# YNM-3000-1.net
KiCad netlist of a schematic drawn in Altium Designer
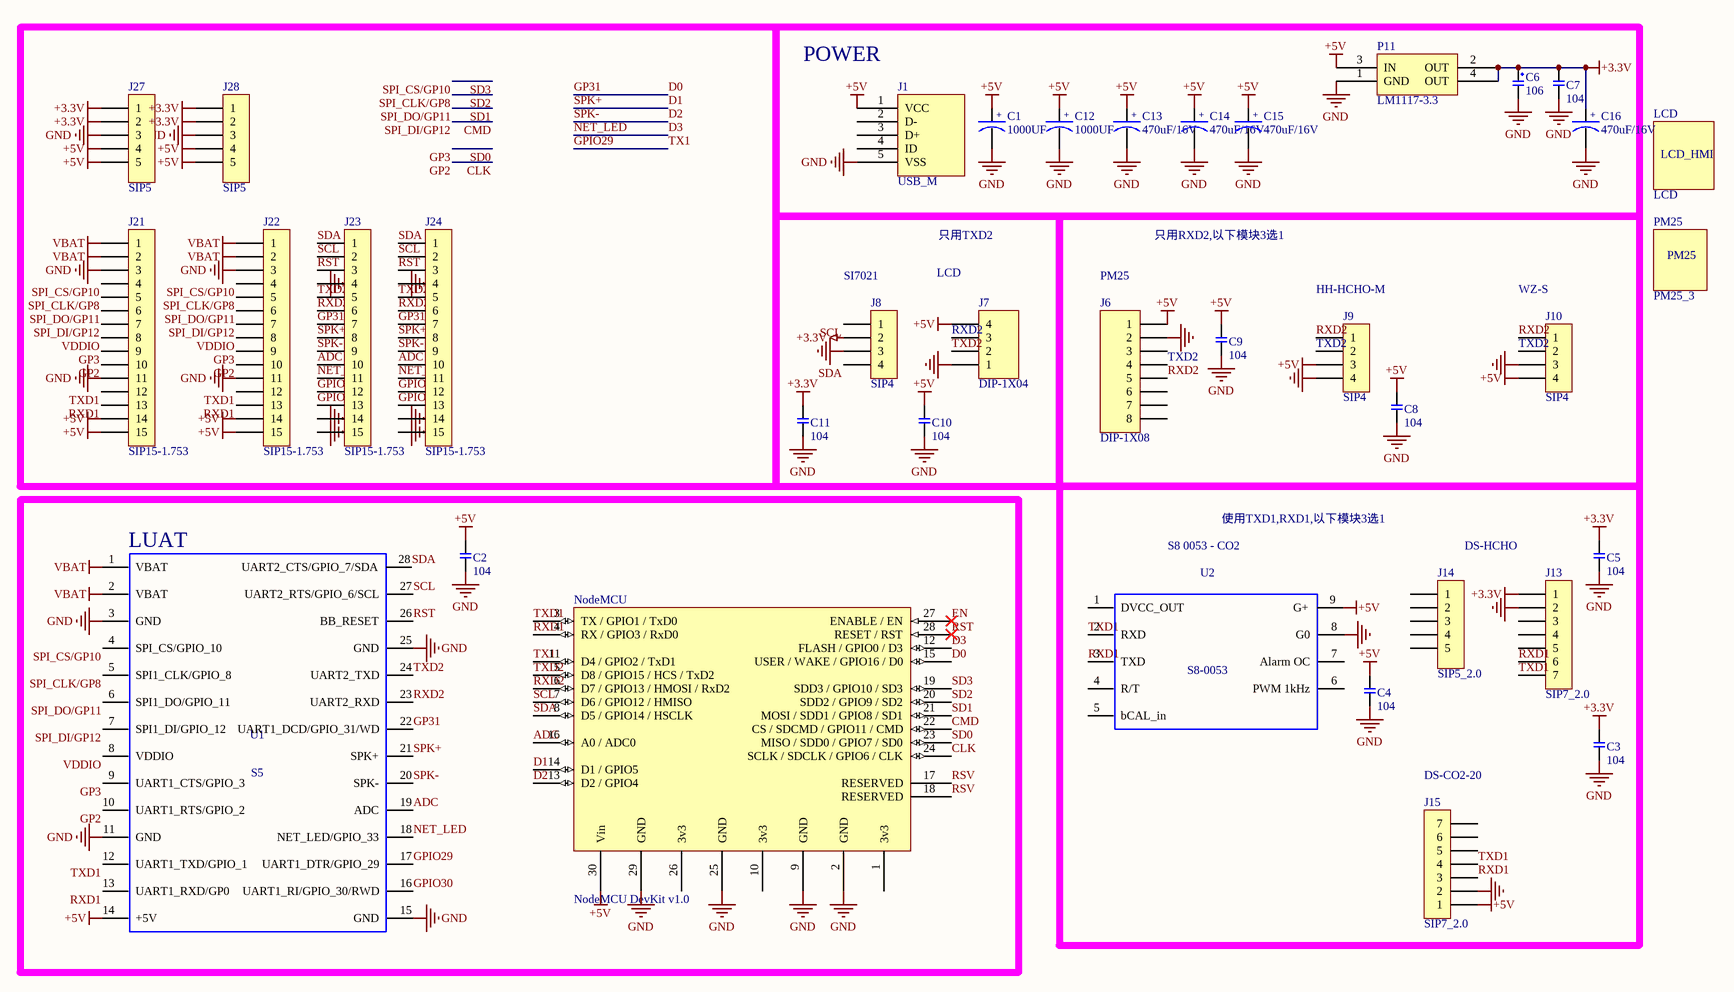
[diagram p0: YNM-3000-1.SchDoc]

(export (version "E")
  (design (tool "Eeschema 10.0.6"))
  (components
    (comp (ref "C1")
      (value "1000UF")
      (footprint "SMD-EC-F10")
      (description "体积（10*10.2MM）")
      (libsource (lib "wyf") (part "SMD-EC-F10"))
    )
    (comp (ref "C2")
      (value "104")
      (footprint "CAP-SMD-0603")
      (description "Cap0603")
      (libsource (lib "wyf") (part "Cap0603"))
    )
    (comp (ref "C3")
      (value "104")
      (footprint "CAP-SMD-0603")
      (description "Cap0603")
      (libsource (lib "wyf") (part "Cap0603"))
    )
    (comp (ref "C4")
      (value "104")
      (footprint "CAP-SMD-0603")
      (description "Cap0603")
      (libsource (lib "wyf") (part "Cap0603"))
    )
    (comp (ref "C5")
      (value "104")
      (footprint "CAP-SMD-0603")
      (description "Cap0603")
      (libsource (lib "wyf") (part "Cap0603"))
    )
    (comp (ref "C6")
      (value "106")
      (footprint "EC3528B")
      (description "CAP-3528")
      (libsource (lib "wyf") (part "CAP-3528"))
    )
    (comp (ref "C7")
      (value "104")
      (footprint "CAP-SMD-0603")
      (description "Cap0603")
      (libsource (lib "wyf") (part "Cap0603"))
    )
    (comp (ref "C8")
      (value "104")
      (footprint "CAP-SMD-0603")
      (description "Cap0603")
      (libsource (lib "wyf") (part "Cap0603"))
    )
    (comp (ref "C9")
      (value "104")
      (footprint "CAP-SMD-0603")
      (description "Cap0603")
      (libsource (lib "wyf") (part "Cap0603"))
    )
    (comp (ref "C10")
      (value "104")
      (footprint "CAP-SMD-0603")
      (description "Cap0603")
      (libsource (lib "wyf") (part "Cap0603"))
    )
    (comp (ref "C11")
      (value "104")
      (footprint "CAP-SMD-0603")
      (description "Cap0603")
      (libsource (lib "wyf") (part "Cap0603"))
    )
    (comp (ref "C12")
      (value "1000UF")
      (footprint "SMD-EC-F10")
      (description "体积（10*10.2MM）")
      (libsource (lib "wyf") (part "SMD-EC-F10"))
    )
    (comp (ref "C13")
      (value "470uF/16V")
      (footprint "SMD-EC-F8")
      (description "体积（8*10.2MM）")
      (libsource (lib "wyf") (part "SMD-EC-F8"))
    )
    (comp (ref "C14")
      (value "470uF/16V")
      (footprint "SMD-EC-F8")
      (description "体积（8*10.2MM）")
      (libsource (lib "wyf") (part "SMD-EC-F8"))
    )
    (comp (ref "C15")
      (value "470uF/16V")
      (footprint "SMD-EC-F8")
      (description "体积（8*10.2MM）")
      (libsource (lib "wyf") (part "SMD-EC-F8"))
    )
    (comp (ref "C16")
      (value "470uF/16V")
      (footprint "SMD-EC-F8")
      (description "体积（8*10.2MM）")
      (libsource (lib "wyf") (part "SMD-EC-F8"))
    )
    (comp (ref "J1")
      (value "USB_M")
      (footprint "USB_MICRO")
      (description "Micro/Mini USB")
      (libsource (lib "wyf") (part "USB_M"))
    )
    (comp (ref "J6")
      (value "DIP-1X08")
      (footprint "1.27*8")
      (description "Header, 8-Pin")
      (fields (field (name "PUBLISHER") "Altium Limited"))
      (libsource (lib "connector") (part "DIP-1X08"))
    )
    (comp (ref "J7")
      (value "DIP-1X04")
      (footprint "XH-1X04-2.5")
      (description "Header, 4-Pin")
      (fields (field (name "PUBLISHER") "Altium Limited"))
      (libsource (lib "connector") (part "DIP-1X04"))
    )
    (comp (ref "J8") (value "SIP4") (footprint "DB-1X4") (libsource (lib "wyf") (part "SIP4")))
    (comp (ref "J9") (value "SIP4") (footprint "DB-1X4") (libsource (lib "wyf") (part "SIP4")))
    (comp (ref "J10") (value "SIP4") (footprint "DB-1X4") (libsource (lib "wyf") (part "SIP4")))
    (comp (ref "J13") (value "SIP7_2.0") (footprint "SIP_2.0_7P") (libsource (lib "") (part "SIP7_2.0_1")))
    (comp (ref "J14") (value "SIP5_2.0") (footprint "SIP_2.0_5P") (libsource (lib "wyf") (part "SIP5_2.0")))
    (comp (ref "J15") (value "SIP7_2.0") (footprint "SIP_2.0_7P") (libsource (lib "wyf") (part "SIP7_2.0")))
    (comp (ref "J21")
      (value "SIP15-1.753")
      (footprint "DB-1X15-1.753")
      (libsource (lib "wyf") (part "SIP15-1.753"))
    )
    (comp (ref "J22")
      (value "SIP15-1.753")
      (footprint "DB-1X15-1.753")
      (libsource (lib "wyf") (part "SIP15-1.753"))
    )
    (comp (ref "J23")
      (value "SIP15-1.753")
      (footprint "DB-1X15-1.753")
      (libsource (lib "wyf") (part "SIP15-1.753"))
    )
    (comp (ref "J24")
      (value "SIP15-1.753")
      (footprint "DB-1X15-1.753")
      (libsource (lib "wyf") (part "SIP15-1.753"))
    )
    (comp (ref "J27") (value "SIP5") (footprint "DB-1X5") (libsource (lib "wyf") (part "SIP5")))
    (comp (ref "J28") (value "SIP5") (footprint "DB-1X5") (libsource (lib "wyf") (part "SIP5")))
    (comp (ref "LCD") (value "LCD") (footprint "LCD") (libsource (lib "wyf") (part "LCD")))
    (comp (ref "NodeMCU")
      (value "NodeMCU DevKit v1.0")
      (footprint "NodeMCU DevKit v1.0 - Inside Labels")
      (libsource (lib "NodeMCU") (part "NodeMCU DevKit v1.0"))
    )
    (comp (ref "P11") (value "LM1117-3.3") (footprint "SOT-223") (libsource (lib "wyf") (part "LM1117")))
    (comp (ref "PM25") (value "PM25_3") (footprint "PM25_3") (libsource (lib "wyf") (part "PM25_3")))
    (comp (ref "U1") (value "S5") (footprint "S5") (libsource (lib "wyf") (part "S5")))
    (comp (ref "U2") (value "S8-0053") (footprint "S8-0053") (libsource (lib "wyf") (part "S8-0053")))
  )
  (nets
    (net (code "1") (name "+3.3V") (class "Default")
      (node (ref "C11") (pin "2") (pinfunction "1_2") (pintype "passive"))
      (node (ref "C16") (pin "1") (pinfunction "1_1") (pintype "passive"))
      (node (ref "C3") (pin "2") (pinfunction "1_2") (pintype "passive"))
      (node (ref "C5") (pin "2") (pinfunction "1_2") (pintype "passive"))
      (node (ref "C6") (pin "1") (pinfunction "0_1") (pintype "passive"))
      (node (ref "C7") (pin "2") (pinfunction "1_2") (pintype "passive"))
      (node (ref "J13") (pin "1") (pinfunction "1_1") (pintype "passive"))
      (node (ref "J27") (pin "1") (pinfunction "1_1") (pintype "passive"))
      (node (ref "J27") (pin "2") (pinfunction "2_2") (pintype "passive"))
      (node (ref "J28") (pin "1") (pinfunction "1_1") (pintype "passive"))
      (node (ref "J28") (pin "2") (pinfunction "2_2") (pintype "passive"))
      (node (ref "J8") (pin "2") (pinfunction "2_2") (pintype "passive"))
      (node (ref "P11") (pin "2") (pinfunction "OUT_2") (pintype "passive"))
      (node (ref "P11") (pin "4") (pinfunction "OUT_4") (pintype "passive"))
    )
    (net (code "2") (name "+5V") (class "Default")
      (node (ref "C1") (pin "1") (pinfunction "1_1") (pintype "passive"))
      (node (ref "C10") (pin "2") (pinfunction "1_2") (pintype "passive"))
      (node (ref "C12") (pin "1") (pinfunction "1_1") (pintype "passive"))
      (node (ref "C13") (pin "1") (pinfunction "1_1") (pintype "passive"))
      (node (ref "C14") (pin "1") (pinfunction "1_1") (pintype "passive"))
      (node (ref "C15") (pin "1") (pinfunction "1_1") (pintype "passive"))
      (node (ref "C2") (pin "2") (pinfunction "1_2") (pintype "passive"))
      (node (ref "C4") (pin "2") (pinfunction "1_2") (pintype "passive"))
      (node (ref "C8") (pin "2") (pinfunction "1_2") (pintype "passive"))
      (node (ref "C9") (pin "2") (pinfunction "1_2") (pintype "passive"))
      (node (ref "J1") (pin "1") (pinfunction "VCC_1") (pintype "passive"))
      (node (ref "J10") (pin "4") (pinfunction "4_4") (pintype "passive"))
      (node (ref "J15") (pin "1") (pinfunction "1_1") (pintype "passive"))
      (node (ref "J21") (pin "14") (pinfunction "14_14") (pintype "passive"))
      (node (ref "J21") (pin "15") (pinfunction "15_15") (pintype "passive"))
      (node (ref "J22") (pin "14") (pinfunction "14_14") (pintype "passive"))
      (node (ref "J22") (pin "15") (pinfunction "15_15") (pintype "passive"))
      (node (ref "J27") (pin "4") (pinfunction "4_4") (pintype "passive"))
      (node (ref "J27") (pin "5") (pinfunction "5_5") (pintype "passive"))
      (node (ref "J28") (pin "4") (pinfunction "4_4") (pintype "passive"))
      (node (ref "J28") (pin "5") (pinfunction "5_5") (pintype "passive"))
      (node (ref "J6") (pin "1") (pinfunction "1_1") (pintype "passive"))
      (node (ref "J7") (pin "4") (pinfunction "4_4") (pintype "passive"))
      (node (ref "J9") (pin "3") (pinfunction "3_3") (pintype "passive"))
      (node (ref "NodeMCU") (pin "30") (pinfunction "Vin_30") (pintype "passive"))
      (node (ref "P11") (pin "3") (pinfunction "IN_3") (pintype "passive"))
      (node (ref "U1") (pin "14") (pinfunction "+5V_14") (pintype "passive"))
      (node (ref "U2") (pin "9") (pinfunction "G+_9") (pintype "passive"))
    )
    (net (code "3") (name "/ADC") (class "Default")
      (node (ref "J23") (pin "10") (pinfunction "10_10") (pintype "passive"))
      (node (ref "J24") (pin "10") (pinfunction "10_10") (pintype "passive"))
      (node (ref "NodeMCU") (pin "16") (pinfunction "A0_/_ADC0_16") (pintype "bidirectional"))
      (node (ref "U1") (pin "19") (pinfunction "ADC_19") (pintype "passive"))
    )
    (net (code "4") (name "/CLK") (class "Default")
      (node (ref "J21") (pin "10") (pinfunction "10_10") (pintype "passive"))
      (node (ref "J22") (pin "10") (pinfunction "10_10") (pintype "passive"))
      (node (ref "NodeMCU") (pin "24") (pinfunction "SCLK_/_SDCLK_/_GPIO6_/_CLK_24") (pintype "bidirectional"))
      (node (ref "U1") (pin "10") (pinfunction "UART1_RTS/GPIO_2_10") (pintype "passive"))
    )
    (net (code "5") (name "/CMD") (class "Default")
      (node (ref "J21") (pin "7") (pinfunction "7_7") (pintype "passive"))
      (node (ref "J22") (pin "7") (pinfunction "7_7") (pintype "passive"))
      (node (ref "NodeMCU") (pin "22") (pinfunction "CS_/_SDCMD_/_GPIO11_/_CMD_22") (pintype "bidirectional"))
      (node (ref "U1") (pin "7") (pinfunction "SPI1_DI/GPIO_12_7") (pintype "passive"))
    )
    (net (code "6") (name "/D0") (class "Default")
      (node (ref "J23") (pin "7") (pinfunction "7_7") (pintype "passive"))
      (node (ref "J24") (pin "7") (pinfunction "7_7") (pintype "passive"))
      (node (ref "NodeMCU") (pin "15") (pinfunction "USER_/_WAKE_/_GPIO16_/_D0_15") (pintype "bidirectional"))
      (node (ref "U1") (pin "22") (pinfunction "UART1_DCD/GPIO_31/WD_22") (pintype "passive"))
    )
    (net (code "7") (name "/D1") (class "Default")
      (node (ref "J23") (pin "8") (pinfunction "8_8") (pintype "passive"))
      (node (ref "J24") (pin "8") (pinfunction "8_8") (pintype "passive"))
      (node (ref "NodeMCU") (pin "14") (pinfunction "D1_/_GPIO5_14") (pintype "bidirectional"))
      (node (ref "U1") (pin "21") (pinfunction "SPK+_21") (pintype "passive"))
    )
    (net (code "8") (name "/D2") (class "Default")
      (node (ref "J23") (pin "9") (pinfunction "9_9") (pintype "passive"))
      (node (ref "J24") (pin "9") (pinfunction "9_9") (pintype "passive"))
      (node (ref "NodeMCU") (pin "13") (pinfunction "D2_/_GPIO4_13") (pintype "bidirectional"))
      (node (ref "U1") (pin "20") (pinfunction "SPK-_20") (pintype "passive"))
    )
    (net (code "9") (name "/D3") (class "Default")
      (node (ref "J23") (pin "11") (pinfunction "11_11") (pintype "passive"))
      (node (ref "J24") (pin "11") (pinfunction "11_11") (pintype "passive"))
      (node (ref "NodeMCU") (pin "12") (pinfunction "FLASH_/_GPIO0_/_D3_12") (pintype "bidirectional"))
      (node (ref "U1") (pin "18") (pinfunction "NET_LED/GPIO_33_18") (pintype "passive"))
    )
    (net (code "10") (name "/EN") (class "Default")
      (node (ref "NodeMCU") (pin "27") (pinfunction "ENABLE_/_EN_27") (pintype "input+no_connect"))
    )
    (net (code "11") (name "/GP3") (class "Default")
      (node (ref "J21") (pin "9") (pinfunction "9_9") (pintype "passive"))
      (node (ref "J22") (pin "9") (pinfunction "9_9") (pintype "passive"))
      (node (ref "NodeMCU") (pin "23") (pinfunction "MISO_/_SDD0_/_GPIO7_/_SD0_23") (pintype "bidirectional"))
      (node (ref "U1") (pin "9") (pinfunction "UART1_CTS/GPIO_3_9") (pintype "passive"))
    )
    (net (code "12") (name "/GPIO29") (class "Default")
      (node (ref "J23") (pin "12") (pinfunction "12_12") (pintype "passive"))
      (node (ref "J24") (pin "12") (pinfunction "12_12") (pintype "passive"))
      (node (ref "NodeMCU") (pin "11") (pinfunction "D4_/_GPIO2_/_TxD1_11") (pintype "bidirectional"))
      (node (ref "U1") (pin "17") (pinfunction "UART1_DTR/GPIO_29_17") (pintype "passive"))
    )
    (net (code "13") (name "/GPIO30") (class "Default")
      (node (ref "J23") (pin "13") (pinfunction "13_13") (pintype "passive"))
      (node (ref "J24") (pin "13") (pinfunction "13_13") (pintype "passive"))
      (node (ref "U1") (pin "16") (pinfunction "UART1_RI/GPIO_30/RWD_16") (pintype "passive"))
    )
    (net (code "14") (name "/RST") (class "Default")
      (node (ref "J23") (pin "3") (pinfunction "3_3") (pintype "passive"))
      (node (ref "J24") (pin "3") (pinfunction "3_3") (pintype "passive"))
      (node (ref "NodeMCU") (pin "28") (pinfunction "RESET_/_RST_28") (pintype "input"))
      (node (ref "U1") (pin "26") (pinfunction "BB_RESET_26") (pintype "passive"))
    )
    (net (code "15") (name "/RSV") (class "Default")
      (node (ref "NodeMCU") (pin "17") (pinfunction "RESERVED_17") (pintype "passive"))
      (node (ref "NodeMCU") (pin "18") (pinfunction "RESERVED_18") (pintype "passive"))
    )
    (net (code "16") (name "/RXD1") (class "Default")
      (node (ref "J13") (pin "6") (pinfunction "6_6") (pintype "passive"))
      (node (ref "J15") (pin "3") (pinfunction "3_3") (pintype "passive"))
      (node (ref "J21") (pin "13") (pinfunction "13_13") (pintype "passive"))
      (node (ref "J22") (pin "13") (pinfunction "13_13") (pintype "passive"))
      (node (ref "NodeMCU") (pin "4") (pinfunction "RX_/_GPIO3_/_RxD0_4") (pintype "bidirectional"))
      (node (ref "U1") (pin "13") (pinfunction "UART1_RXD/GP0_13") (pintype "passive"))
      (node (ref "U2") (pin "3") (pinfunction "TXD_3") (pintype "passive"))
    )
    (net (code "17") (name "/RXD2") (class "Default")
      (node (ref "J10") (pin "1") (pinfunction "1_1") (pintype "passive"))
      (node (ref "J23") (pin "6") (pinfunction "6_6") (pintype "passive"))
      (node (ref "J24") (pin "6") (pinfunction "6_6") (pintype "passive"))
      (node (ref "J6") (pin "5") (pinfunction "5_5") (pintype "passive"))
      (node (ref "J9") (pin "1") (pinfunction "1_1") (pintype "passive"))
      (node (ref "NodeMCU") (pin "6") (pinfunction "D7_/_GPIO13_/_HMOSI_/_RxD2_6") (pintype "bidirectional"))
      (node (ref "U1") (pin "23") (pinfunction "UART2_RXD_23") (pintype "passive"))
    )
    (net (code "18") (name "/SCL") (class "Default")
      (node (ref "J23") (pin "2") (pinfunction "2_2") (pintype "passive"))
      (node (ref "J24") (pin "2") (pinfunction "2_2") (pintype "passive"))
      (node (ref "J8") (pin "1") (pinfunction "1_1") (pintype "passive"))
      (node (ref "NodeMCU") (pin "7") (pinfunction "D6_/_GPIO12_/_HMISO_7") (pintype "bidirectional"))
      (node (ref "U1") (pin "27") (pinfunction "UART2_RTS/GPIO_6/SCL_27") (pintype "passive"))
    )
    (net (code "19") (name "/SD1") (class "Default")
      (node (ref "J21") (pin "6") (pinfunction "6_6") (pintype "passive"))
      (node (ref "J22") (pin "6") (pinfunction "6_6") (pintype "passive"))
      (node (ref "NodeMCU") (pin "21") (pinfunction "MOSI_/_SDD1_/_GPIO8_/_SD1_21") (pintype "bidirectional"))
      (node (ref "U1") (pin "6") (pinfunction "SPI1_DO/GPIO_11_6") (pintype "passive"))
    )
    (net (code "20") (name "/SD2") (class "Default")
      (node (ref "J21") (pin "5") (pinfunction "5_5") (pintype "passive"))
      (node (ref "J22") (pin "5") (pinfunction "5_5") (pintype "passive"))
      (node (ref "NodeMCU") (pin "20") (pinfunction "SDD2_/_GPIO9_/_SD2_20") (pintype "bidirectional"))
      (node (ref "U1") (pin "5") (pinfunction "SPI1_CLK/GPIO_8_5") (pintype "passive"))
    )
    (net (code "21") (name "/SD3") (class "Default")
      (node (ref "J21") (pin "4") (pinfunction "4_4") (pintype "passive"))
      (node (ref "J22") (pin "4") (pinfunction "4_4") (pintype "passive"))
      (node (ref "NodeMCU") (pin "19") (pinfunction "SDD3_/_GPIO10_/_SD3_19") (pintype "bidirectional"))
      (node (ref "U1") (pin "4") (pinfunction "SPI_CS/GPIO_10_4") (pintype "passive"))
    )
    (net (code "22") (name "/SDA") (class "Default")
      (node (ref "J23") (pin "1") (pinfunction "1_1") (pintype "passive"))
      (node (ref "J24") (pin "1") (pinfunction "1_1") (pintype "passive"))
      (node (ref "J8") (pin "4") (pinfunction "4_4") (pintype "passive"))
      (node (ref "NodeMCU") (pin "8") (pinfunction "D5_/_GPIO14_/_HSCLK_8") (pintype "bidirectional"))
      (node (ref "U1") (pin "28") (pinfunction "UART2_CTS/GPIO_7/SDA_28") (pintype "passive"))
    )
    (net (code "23") (name "/TXD1") (class "Default")
      (node (ref "J13") (pin "7") (pinfunction "7_7") (pintype "passive"))
      (node (ref "J15") (pin "4") (pinfunction "4_4") (pintype "passive"))
      (node (ref "J21") (pin "12") (pinfunction "12_12") (pintype "passive"))
      (node (ref "J22") (pin "12") (pinfunction "12_12") (pintype "passive"))
      (node (ref "NodeMCU") (pin "3") (pinfunction "TX_/_GPIO1_/_TxD0_3") (pintype "bidirectional"))
      (node (ref "U1") (pin "12") (pinfunction "UART1_TXD/GPIO_1_12") (pintype "passive"))
      (node (ref "U2") (pin "2") (pinfunction "RXD_2") (pintype "passive"))
    )
    (net (code "24") (name "/TXD2") (class "Default")
      (node (ref "J23") (pin "5") (pinfunction "5_5") (pintype "passive"))
      (node (ref "J24") (pin "5") (pinfunction "5_5") (pintype "passive"))
      (node (ref "J7") (pin "2") (pinfunction "2_2") (pintype "passive"))
      (node (ref "NodeMCU") (pin "5") (pinfunction "D8_/_GPIO15_/_HCS_/_TxD2_5") (pintype "bidirectional"))
      (node (ref "U1") (pin "24") (pinfunction "UART2_TXD_24") (pintype "passive"))
    )
    (net (code "25") (name "/VDDIO") (class "Default")
      (node (ref "J21") (pin "8") (pinfunction "8_8") (pintype "passive"))
      (node (ref "J22") (pin "8") (pinfunction "8_8") (pintype "passive"))
      (node (ref "U1") (pin "8") (pinfunction "VDDIO_8") (pintype "passive"))
    )
    (net (code "26") (name "GND") (class "Default")
      (node (ref "C1") (pin "2") (pinfunction "2_2") (pintype "passive"))
      (node (ref "C10") (pin "1") (pinfunction "0_1") (pintype "passive"))
      (node (ref "C11") (pin "1") (pinfunction "0_1") (pintype "passive"))
      (node (ref "C12") (pin "2") (pinfunction "2_2") (pintype "passive"))
      (node (ref "C13") (pin "2") (pinfunction "2_2") (pintype "passive"))
      (node (ref "C14") (pin "2") (pinfunction "2_2") (pintype "passive"))
      (node (ref "C15") (pin "2") (pinfunction "2_2") (pintype "passive"))
      (node (ref "C16") (pin "2") (pinfunction "2_2") (pintype "passive"))
      (node (ref "C2") (pin "1") (pinfunction "0_1") (pintype "passive"))
      (node (ref "C3") (pin "1") (pinfunction "0_1") (pintype "passive"))
      (node (ref "C4") (pin "1") (pinfunction "0_1") (pintype "passive"))
      (node (ref "C5") (pin "1") (pinfunction "0_1") (pintype "passive"))
      (node (ref "C6") (pin "2") (pinfunction "1_2") (pintype "passive"))
      (node (ref "C7") (pin "1") (pinfunction "0_1") (pintype "passive"))
      (node (ref "C8") (pin "1") (pinfunction "0_1") (pintype "passive"))
      (node (ref "C9") (pin "1") (pinfunction "0_1") (pintype "passive"))
      (node (ref "J1") (pin "5") (pinfunction "VSS_5") (pintype "passive"))
      (node (ref "J10") (pin "3") (pinfunction "3_3") (pintype "passive"))
      (node (ref "J13") (pin "2") (pinfunction "2_2") (pintype "passive"))
      (node (ref "J15") (pin "2") (pinfunction "2_2") (pintype "passive"))
      (node (ref "J21") (pin "11") (pinfunction "11_11") (pintype "passive"))
      (node (ref "J21") (pin "3") (pinfunction "3_3") (pintype "passive"))
      (node (ref "J22") (pin "11") (pinfunction "11_11") (pintype "passive"))
      (node (ref "J22") (pin "3") (pinfunction "3_3") (pintype "passive"))
      (node (ref "J23") (pin "14") (pinfunction "14_14") (pintype "passive"))
      (node (ref "J23") (pin "15") (pinfunction "15_15") (pintype "passive"))
      (node (ref "J23") (pin "4") (pinfunction "4_4") (pintype "passive"))
      (node (ref "J24") (pin "14") (pinfunction "14_14") (pintype "passive"))
      (node (ref "J24") (pin "15") (pinfunction "15_15") (pintype "passive"))
      (node (ref "J24") (pin "4") (pinfunction "4_4") (pintype "passive"))
      (node (ref "J27") (pin "3") (pinfunction "3_3") (pintype "passive"))
      (node (ref "J28") (pin "3") (pinfunction "3_3") (pintype "passive"))
      (node (ref "J6") (pin "2") (pinfunction "2_2") (pintype "passive"))
      (node (ref "J7") (pin "1") (pinfunction "1_1") (pintype "passive"))
      (node (ref "J8") (pin "3") (pinfunction "3_3") (pintype "passive"))
      (node (ref "J9") (pin "4") (pinfunction "4_4") (pintype "passive"))
      (node (ref "NodeMCU") (pin "2") (pinfunction "GND_2") (pintype "power_in"))
      (node (ref "NodeMCU") (pin "25") (pinfunction "GND_25") (pintype "power_in"))
      (node (ref "NodeMCU") (pin "29") (pinfunction "GND_29") (pintype "passive"))
      (node (ref "NodeMCU") (pin "9") (pinfunction "GND_9") (pintype "power_in"))
      (node (ref "P11") (pin "1") (pinfunction "GND_1") (pintype "passive"))
      (node (ref "U1") (pin "11") (pinfunction "GND_11") (pintype "passive"))
      (node (ref "U1") (pin "15") (pinfunction "GND_15") (pintype "passive"))
      (node (ref "U1") (pin "25") (pinfunction "GND_25") (pintype "passive"))
      (node (ref "U1") (pin "3") (pinfunction "GND_3") (pintype "passive"))
      (node (ref "U2") (pin "8") (pinfunction "G0_8") (pintype "passive"))
    )
    (net (code "27") (name "VBAT") (class "Default")
      (node (ref "J21") (pin "1") (pinfunction "1_1") (pintype "passive"))
      (node (ref "J21") (pin "2") (pinfunction "2_2") (pintype "passive"))
      (node (ref "J22") (pin "1") (pinfunction "1_1") (pintype "passive"))
      (node (ref "J22") (pin "2") (pinfunction "2_2") (pintype "passive"))
      (node (ref "U1") (pin "1") (pinfunction "VBAT_1") (pintype "passive"))
      (node (ref "U1") (pin "2") (pinfunction "VBAT_2") (pintype "passive"))
    )
    (net (code "28") (name "unconnected-(J1-D+-Pad3)") (class "Default")
      (node (ref "J1") (pin "3") (pinfunction "D+_3") (pintype "passive"))
    )
    (net (code "29") (name "unconnected-(J1-D--Pad2)") (class "Default")
      (node (ref "J1") (pin "2") (pinfunction "D-_2") (pintype "passive"))
    )
    (net (code "30") (name "unconnected-(J1-ID-Pad4)") (class "Default")
      (node (ref "J1") (pin "4") (pinfunction "ID_4") (pintype "passive"))
    )
    (net (code "31") (name "unconnected-(J6-Pad3)") (class "Default")
      (node (ref "J6") (pin "3") (pinfunction "3_3") (pintype "passive"))
    )
    (net (code "32") (name "unconnected-(J6-Pad4)") (class "Default")
      (node (ref "J6") (pin "4") (pinfunction "4_4") (pintype "passive"))
    )
    (net (code "33") (name "unconnected-(J6-Pad6)") (class "Default")
      (node (ref "J6") (pin "6") (pinfunction "6_6") (pintype "passive"))
    )
    (net (code "34") (name "unconnected-(J6-Pad7)") (class "Default")
      (node (ref "J6") (pin "7") (pinfunction "7_7") (pintype "passive"))
    )
    (net (code "35") (name "unconnected-(J6-Pad8)") (class "Default")
      (node (ref "J6") (pin "8") (pinfunction "8_8") (pintype "passive"))
    )
    (net (code "36") (name "unconnected-(J7-Pad3)") (class "Default")
      (node (ref "J7") (pin "3") (pinfunction "3_3") (pintype "passive"))
    )
    (net (code "37") (name "unconnected-(J9-Pad2)") (class "Default")
      (node (ref "J9") (pin "2") (pinfunction "2_2") (pintype "passive"))
    )
    (net (code "38") (name "unconnected-(J10-Pad2)") (class "Default")
      (node (ref "J10") (pin "2") (pinfunction "2_2") (pintype "passive"))
    )
    (net (code "39") (name "unconnected-(J13-Pad3)") (class "Default")
      (node (ref "J13") (pin "3") (pinfunction "3_3") (pintype "passive"))
    )
    (net (code "40") (name "unconnected-(J13-Pad4)") (class "Default")
      (node (ref "J13") (pin "4") (pinfunction "4_4") (pintype "passive"))
    )
    (net (code "41") (name "unconnected-(J13-Pad5)") (class "Default")
      (node (ref "J13") (pin "5") (pinfunction "5_5") (pintype "passive"))
    )
    (net (code "42") (name "unconnected-(J14-Pad1)") (class "Default")
      (node (ref "J14") (pin "1") (pinfunction "1_1") (pintype "passive"))
    )
    (net (code "43") (name "unconnected-(J14-Pad2)") (class "Default")
      (node (ref "J14") (pin "2") (pinfunction "2_2") (pintype "passive"))
    )
    (net (code "44") (name "unconnected-(J14-Pad3)") (class "Default")
      (node (ref "J14") (pin "3") (pinfunction "3_3") (pintype "passive"))
    )
    (net (code "45") (name "unconnected-(J14-Pad4)") (class "Default")
      (node (ref "J14") (pin "4") (pinfunction "4_4") (pintype "passive"))
    )
    (net (code "46") (name "unconnected-(J14-Pad5)") (class "Default")
      (node (ref "J14") (pin "5") (pinfunction "5_5") (pintype "passive"))
    )
    (net (code "47") (name "unconnected-(J15-Pad5)") (class "Default")
      (node (ref "J15") (pin "5") (pinfunction "5_5") (pintype "passive"))
    )
    (net (code "48") (name "unconnected-(J15-Pad6)") (class "Default")
      (node (ref "J15") (pin "6") (pinfunction "6_6") (pintype "passive"))
    )
    (net (code "49") (name "unconnected-(J15-Pad7)") (class "Default")
      (node (ref "J15") (pin "7") (pinfunction "7_7") (pintype "passive"))
    )
    (net (code "50") (name "unconnected-(NodeMCU-3v3-Pad1)") (class "Default")
      (node (ref "NodeMCU") (pin "1") (pinfunction "3v3_1") (pintype "power_in"))
    )
    (net (code "51") (name "unconnected-(NodeMCU-3v3-Pad10)") (class "Default")
      (node (ref "NodeMCU") (pin "10") (pinfunction "3v3_10") (pintype "power_in"))
    )
    (net (code "52") (name "unconnected-(NodeMCU-3v3-Pad26)") (class "Default")
      (node (ref "NodeMCU") (pin "26") (pinfunction "3v3_26") (pintype "power_in"))
    )
    (net (code "53") (name "unconnected-(U2-Alarm_OC-Pad7)") (class "Default")
      (node (ref "U2") (pin "7") (pinfunction "Alarm_OC_7") (pintype "passive"))
    )
    (net (code "54") (name "unconnected-(U2-DVCC_OUT-Pad1)") (class "Default")
      (node (ref "U2") (pin "1") (pinfunction "DVCC_OUT_1") (pintype "passive"))
    )
    (net (code "55") (name "unconnected-(U2-PWM_1kHz-Pad6)") (class "Default")
      (node (ref "U2") (pin "6") (pinfunction "PWM_1kHz_6") (pintype "passive"))
    )
    (net (code "56") (name "unconnected-(U2-R{slash}T-Pad4)") (class "Default")
      (node (ref "U2") (pin "4") (pinfunction "R/T_4") (pintype "passive"))
    )
    (net (code "57") (name "unconnected-(U2-bCAL_in-Pad5)") (class "Default")
      (node (ref "U2") (pin "5") (pinfunction "bCAL_in_5") (pintype "passive"))
    )
  )
)
